# Adafruit_RGB_Matrix_FeatherWing.net
KiCad netlist of a schematic drawn in EAGLE
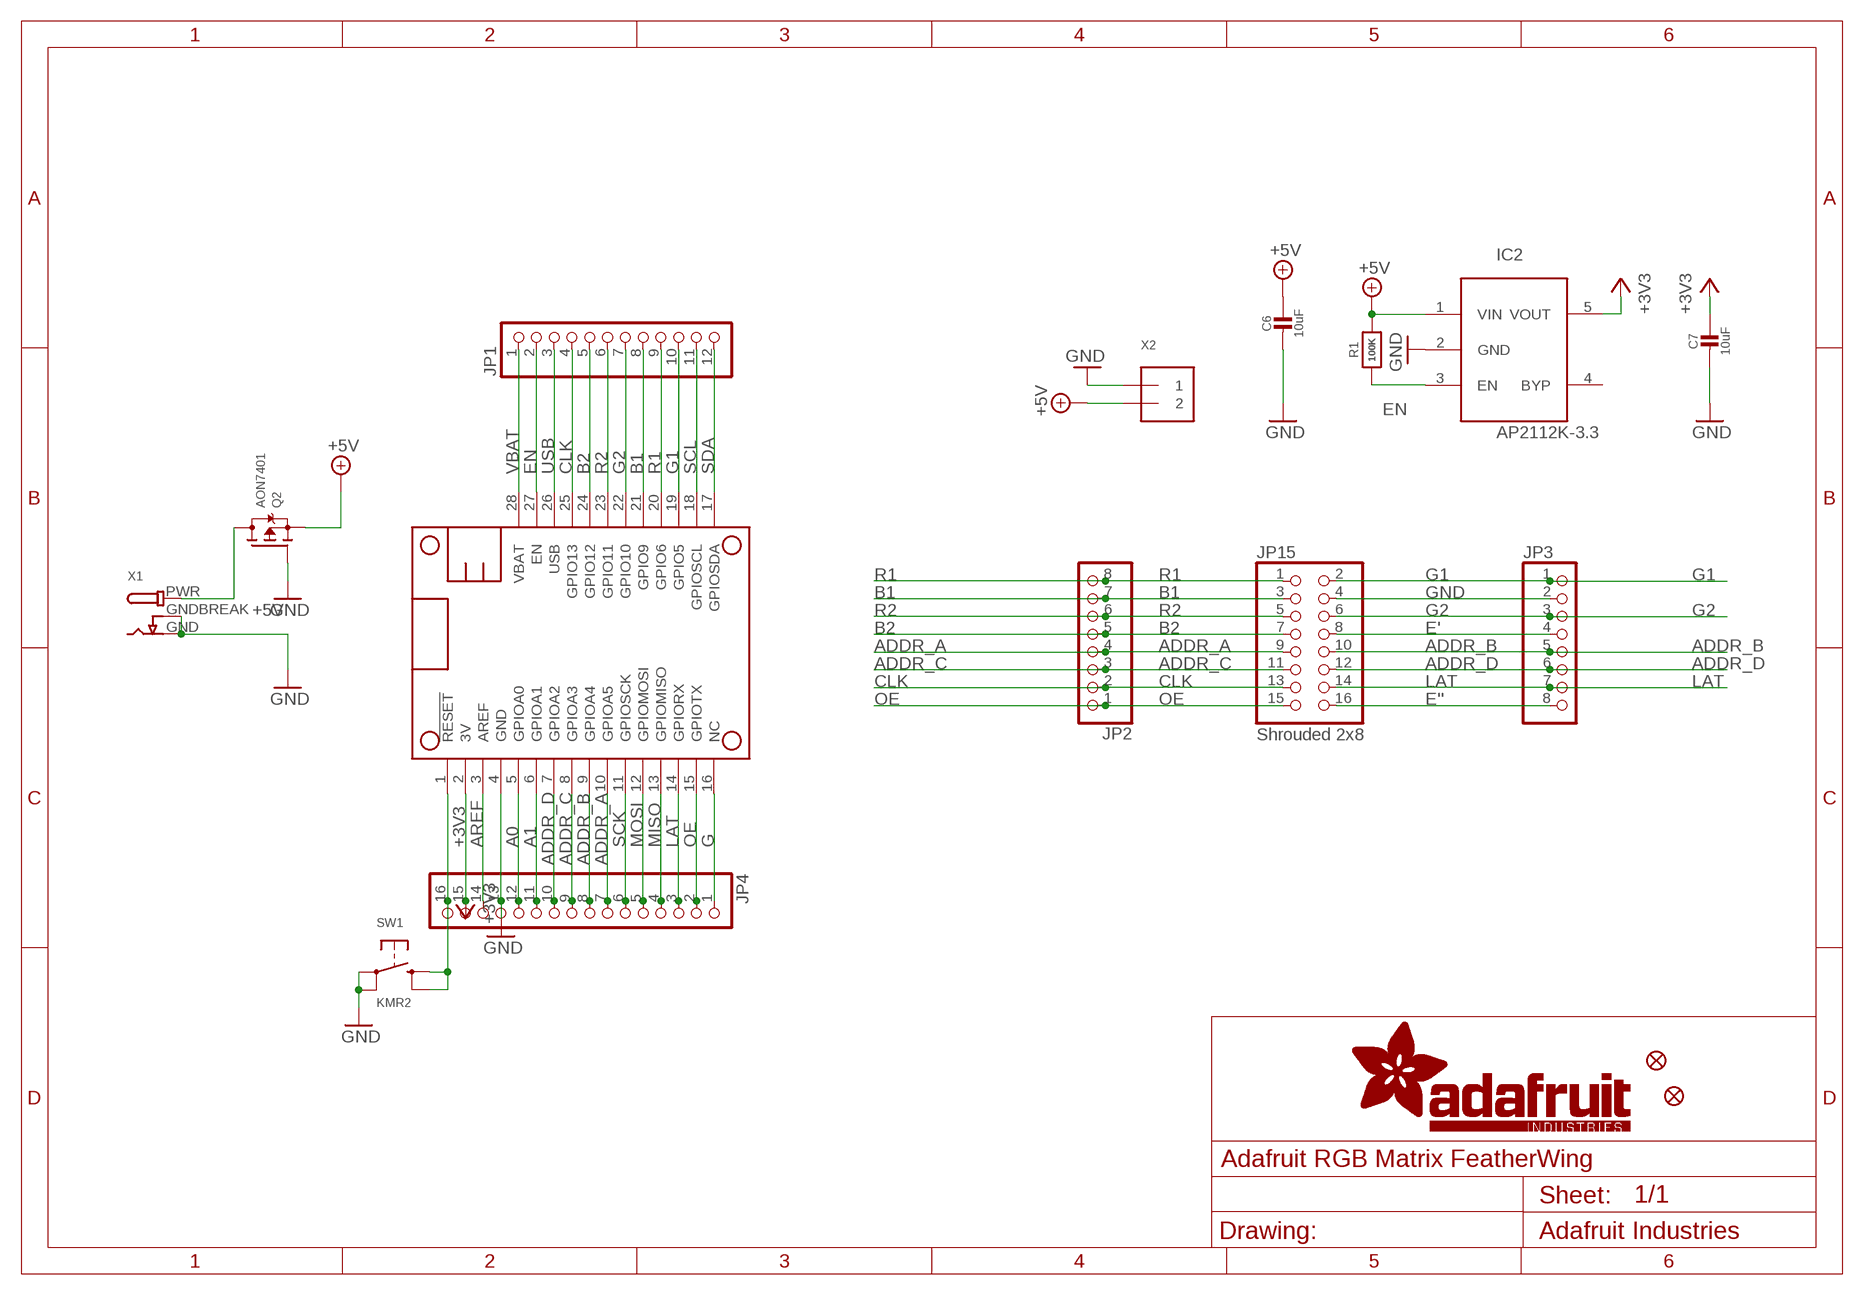
[diagram p0: schematic, sheet 1]

(export (version "E")
  (design (tool "Eeschema 10.0.6"))
  (components
    (comp (ref "C6")
      (value "10uF")
      (footprint "eagle-import:0805-NO")
      (libsource (lib "eagle-import") (part "CAP_CERAMIC0805-NOOUTLINE"))
    )
    (comp (ref "C7")
      (value "10uF")
      (footprint "eagle-import:0805-NO")
      (libsource (lib "eagle-import") (part "CAP_CERAMIC0805-NOOUTLINE"))
    )
    (comp (ref "FID1")
      (value "FIDUCIAL_1MM")
      (footprint "eagle-import:FIDUCIAL_1MM")
      (libsource (lib "eagle-import") (part "FIDUCIAL_1MM"))
    )
    (comp (ref "FID3")
      (value "FIDUCIAL_1MM")
      (footprint "eagle-import:FIDUCIAL_1MM")
      (libsource (lib "eagle-import") (part "FIDUCIAL_1MM"))
    )
    (comp (ref "IC2")
      (value "AP2112K-3.3")
      (footprint "eagle-import:SOT23-5L")
      (libsource (lib "eagle-import") (part "LP298XS"))
    )
    (comp (ref "JP1")
      (value "HEADER-1X12")
      (footprint "eagle-import:1X12_ROUND")
      (libsource (lib "eagle-import") (part "HEADER-1X12"))
    )
    (comp (ref "JP2")
      (value "HEADER-1X870MIL")
      (footprint "eagle-import:1X08_ROUND_70")
      (libsource (lib "eagle-import") (part "HEADER-1X870MIL"))
    )
    (comp (ref "JP3")
      (value "HEADER-1X870MIL")
      (footprint "eagle-import:1X08_ROUND_70")
      (libsource (lib "eagle-import") (part "HEADER-1X870MIL"))
    )
    (comp (ref "JP4")
      (value "HEADER-1X16ROUND")
      (footprint "eagle-import:1X16_ROUND")
      (libsource (lib "eagle-import") (part "HEADER-1X16ROUND"))
    )
    (comp (ref "JP15")
      (value "Shrouded 2x8")
      (footprint "eagle-import:2X08_SHROUDED")
      (libsource (lib "eagle-import") (part "HEADER-2X8_SHROUDED"))
    )
    (comp (ref "MS1")
      (value "FEATHERWING")
      (footprint "eagle-import:FEATHERWING")
      (libsource (lib "eagle-import") (part "FEATHERWING"))
    )
    (comp (ref "Q2")
      (value "AON7401")
      (footprint "eagle-import:POWERDI3333")
      (libsource (lib "eagle-import") (part "MOSFET-P-POWERDI3333"))
    )
    (comp (ref "R1")
      (value "100K")
      (footprint "eagle-import:0603-NO")
      (libsource (lib "eagle-import") (part "RESISTOR_0603_NOOUT"))
    )
    (comp (ref "SW1")
      (value "KMR2")
      (footprint "eagle-import:BTN_KMR2_4.6X2.8")
      (libsource (lib "eagle-import") (part "SWITCH_TACT_SMT4.6X2.8"))
    )
    (comp (ref "X1")
      (value "DCBARRELPTH")
      (footprint "eagle-import:DCJACK_2MM_PTH")
      (libsource (lib "eagle-import") (part "DCBARRELPTH"))
    )
    (comp (ref "X2")
      (value "TERMBLOCK_1X2_5.08MM")
      (footprint "eagle-import:TERMBLOCK_508_1X2")
      (libsource (lib "eagle-import") (part "TERMBLOCK_1X2_5.08MM"))
    )
  )
  (nets
    (net (code "1") (name "+3V3") (class "Default")
      (node (ref "C7") (pin "1") (pinfunction "1_1") (pintype "passive"))
      (node (ref "IC2") (pin "5") (pinfunction "VOUT_5") (pintype "bidirectional"))
      (node (ref "JP4") (pin "15") (pinfunction "15_15") (pintype "passive"))
      (node (ref "MS1") (pin "2") (pinfunction "3V_2") (pintype "power_in"))
    )
    (net (code "2") (name "+5V") (class "Default")
      (node (ref "C6") (pin "1") (pinfunction "1_1") (pintype "passive"))
      (node (ref "IC2") (pin "1") (pinfunction "VIN_1") (pintype "bidirectional"))
      (node (ref "Q2") (pin "1") (pinfunction "S_1") (pintype "passive"))
      (node (ref "Q2") (pin "2") (pinfunction "S_2") (pintype "passive"))
      (node (ref "Q2") (pin "3") (pinfunction "S_3") (pintype "passive"))
      (node (ref "R1") (pin "2") (pinfunction "2_2") (pintype "passive"))
      (node (ref "X2") (pin "P$4") (pinfunction "2_P$4") (pintype "passive"))
    )
    (net (code "3") (name "/A0") (class "Default")
      (node (ref "JP4") (pin "12") (pinfunction "12_12") (pintype "passive"))
      (node (ref "MS1") (pin "5") (pinfunction "GPIOA0_5") (pintype "bidirectional"))
    )
    (net (code "4") (name "/A1") (class "Default")
      (node (ref "JP4") (pin "11") (pinfunction "11_11") (pintype "passive"))
      (node (ref "MS1") (pin "6") (pinfunction "GPIOA1_6") (pintype "bidirectional"))
    )
    (net (code "5") (name "/ADDR_A") (class "Default")
      (node (ref "JP15") (pin "9") (pinfunction "9_9") (pintype "passive"))
      (node (ref "JP2") (pin "4") (pinfunction "4_4") (pintype "passive"))
      (node (ref "JP4") (pin "7") (pinfunction "7_7") (pintype "passive"))
      (node (ref "MS1") (pin "10") (pinfunction "GPIOA5_10") (pintype "bidirectional"))
    )
    (net (code "6") (name "/ADDR_B") (class "Default")
      (node (ref "JP15") (pin "10") (pinfunction "10_10") (pintype "passive"))
      (node (ref "JP3") (pin "5") (pinfunction "5_5") (pintype "passive"))
      (node (ref "JP4") (pin "8") (pinfunction "8_8") (pintype "passive"))
      (node (ref "MS1") (pin "9") (pinfunction "GPIOA4_9") (pintype "bidirectional"))
    )
    (net (code "7") (name "/ADDR_C") (class "Default")
      (node (ref "JP15") (pin "11") (pinfunction "11_11") (pintype "passive"))
      (node (ref "JP2") (pin "3") (pinfunction "3_3") (pintype "passive"))
      (node (ref "JP4") (pin "9") (pinfunction "9_9") (pintype "passive"))
      (node (ref "MS1") (pin "8") (pinfunction "GPIOA3_8") (pintype "bidirectional"))
    )
    (net (code "8") (name "/ADDR_D") (class "Default")
      (node (ref "JP15") (pin "12") (pinfunction "12_12") (pintype "passive"))
      (node (ref "JP3") (pin "6") (pinfunction "6_6") (pintype "passive"))
      (node (ref "JP4") (pin "10") (pinfunction "10_10") (pintype "passive"))
      (node (ref "MS1") (pin "7") (pinfunction "GPIOA2_7") (pintype "bidirectional"))
    )
    (net (code "9") (name "/AREF") (class "Default")
      (node (ref "JP4") (pin "14") (pinfunction "14_14") (pintype "passive"))
      (node (ref "MS1") (pin "3") (pinfunction "AREF_3") (pintype "passive"))
    )
    (net (code "10") (name "/B1") (class "Default")
      (node (ref "JP1") (pin "8") (pinfunction "8_8") (pintype "passive"))
      (node (ref "JP15") (pin "3") (pinfunction "3_3") (pintype "passive"))
      (node (ref "JP2") (pin "7") (pinfunction "7_7") (pintype "passive"))
      (node (ref "MS1") (pin "21") (pinfunction "GPIO9_21") (pintype "bidirectional"))
    )
    (net (code "11") (name "/B2") (class "Default")
      (node (ref "JP1") (pin "5") (pinfunction "5_5") (pintype "passive"))
      (node (ref "JP15") (pin "7") (pinfunction "7_7") (pintype "passive"))
      (node (ref "JP2") (pin "5") (pinfunction "5_5") (pintype "passive"))
      (node (ref "MS1") (pin "24") (pinfunction "GPIO12_24") (pintype "bidirectional"))
    )
    (net (code "12") (name "/CLK") (class "Default")
      (node (ref "JP1") (pin "4") (pinfunction "4_4") (pintype "passive"))
      (node (ref "JP15") (pin "13") (pinfunction "13_13") (pintype "passive"))
      (node (ref "JP2") (pin "2") (pinfunction "2_2") (pintype "passive"))
      (node (ref "MS1") (pin "25") (pinfunction "GPIO13_25") (pintype "bidirectional"))
    )
    (net (code "13") (name "/E'") (class "Default")
      (node (ref "JP15") (pin "8") (pinfunction "8_8") (pintype "passive"))
      (node (ref "JP3") (pin "4") (pinfunction "4_4") (pintype "passive"))
    )
    (net (code "14") (name "/E''") (class "Default")
      (node (ref "JP15") (pin "16") (pinfunction "16_16") (pintype "passive"))
      (node (ref "JP3") (pin "8") (pinfunction "8_8") (pintype "passive"))
    )
    (net (code "15") (name "/EN") (class "Default")
      (node (ref "IC2") (pin "3") (pinfunction "EN_3") (pintype "bidirectional"))
      (node (ref "JP1") (pin "2") (pinfunction "2_2") (pintype "passive"))
      (node (ref "MS1") (pin "27") (pinfunction "EN_27") (pintype "passive"))
      (node (ref "R1") (pin "1") (pinfunction "1_1") (pintype "passive"))
    )
    (net (code "16") (name "/G") (class "Default")
      (node (ref "JP4") (pin "1") (pinfunction "1_1") (pintype "passive"))
      (node (ref "MS1") (pin "16") (pinfunction "NC_16") (pintype "passive"))
    )
    (net (code "17") (name "/G1") (class "Default")
      (node (ref "JP1") (pin "10") (pinfunction "10_10") (pintype "passive"))
      (node (ref "JP15") (pin "2") (pinfunction "2_2") (pintype "passive"))
      (node (ref "JP3") (pin "1") (pinfunction "1_1") (pintype "passive"))
      (node (ref "MS1") (pin "19") (pinfunction "GPIO5_19") (pintype "bidirectional"))
    )
    (net (code "18") (name "/G2") (class "Default")
      (node (ref "JP1") (pin "7") (pinfunction "7_7") (pintype "passive"))
      (node (ref "JP15") (pin "6") (pinfunction "6_6") (pintype "passive"))
      (node (ref "JP3") (pin "3") (pinfunction "3_3") (pintype "passive"))
      (node (ref "MS1") (pin "22") (pinfunction "GPIO10_22") (pintype "bidirectional"))
    )
    (net (code "19") (name "/LAT") (class "Default")
      (node (ref "JP15") (pin "14") (pinfunction "14_14") (pintype "passive"))
      (node (ref "JP3") (pin "7") (pinfunction "7_7") (pintype "passive"))
      (node (ref "JP4") (pin "3") (pinfunction "3_3") (pintype "passive"))
      (node (ref "MS1") (pin "14") (pinfunction "GPIORX_14") (pintype "bidirectional"))
    )
    (net (code "20") (name "/MISO") (class "Default")
      (node (ref "JP4") (pin "4") (pinfunction "4_4") (pintype "passive"))
      (node (ref "MS1") (pin "13") (pinfunction "GPIOMISO_13") (pintype "bidirectional"))
    )
    (net (code "21") (name "/MOSI") (class "Default")
      (node (ref "JP4") (pin "5") (pinfunction "5_5") (pintype "passive"))
      (node (ref "MS1") (pin "12") (pinfunction "GPIOMOSI_12") (pintype "bidirectional"))
    )
    (net (code "22") (name "/OE") (class "Default")
      (node (ref "JP15") (pin "15") (pinfunction "15_15") (pintype "passive"))
      (node (ref "JP2") (pin "1") (pinfunction "1_1") (pintype "passive"))
      (node (ref "JP4") (pin "2") (pinfunction "2_2") (pintype "passive"))
      (node (ref "MS1") (pin "15") (pinfunction "GPIOTX_15") (pintype "bidirectional"))
    )
    (net (code "23") (name "/R1") (class "Default")
      (node (ref "JP1") (pin "9") (pinfunction "9_9") (pintype "passive"))
      (node (ref "JP15") (pin "1") (pinfunction "1_1") (pintype "passive"))
      (node (ref "JP2") (pin "8") (pinfunction "8_8") (pintype "passive"))
      (node (ref "MS1") (pin "20") (pinfunction "GPIO6_20") (pintype "bidirectional"))
    )
    (net (code "24") (name "/R2") (class "Default")
      (node (ref "JP1") (pin "6") (pinfunction "6_6") (pintype "passive"))
      (node (ref "JP15") (pin "5") (pinfunction "5_5") (pintype "passive"))
      (node (ref "JP2") (pin "6") (pinfunction "6_6") (pintype "passive"))
      (node (ref "MS1") (pin "23") (pinfunction "GPIO11_23") (pintype "bidirectional"))
    )
    (net (code "25") (name "/SCK") (class "Default")
      (node (ref "JP4") (pin "6") (pinfunction "6_6") (pintype "passive"))
      (node (ref "MS1") (pin "11") (pinfunction "GPIOSCK_11") (pintype "bidirectional"))
    )
    (net (code "26") (name "/SCL") (class "Default")
      (node (ref "JP1") (pin "11") (pinfunction "11_11") (pintype "passive"))
      (node (ref "MS1") (pin "18") (pinfunction "GPIOSCL_18") (pintype "bidirectional"))
    )
    (net (code "27") (name "/SDA") (class "Default")
      (node (ref "JP1") (pin "12") (pinfunction "12_12") (pintype "passive"))
      (node (ref "MS1") (pin "17") (pinfunction "GPIOSDA_17") (pintype "bidirectional"))
    )
    (net (code "28") (name "/USB") (class "Default")
      (node (ref "JP1") (pin "3") (pinfunction "3_3") (pintype "passive"))
      (node (ref "MS1") (pin "26") (pinfunction "USB_26") (pintype "power_in"))
    )
    (net (code "29") (name "/VBAT") (class "Default")
      (node (ref "JP1") (pin "1") (pinfunction "1_1") (pintype "passive"))
      (node (ref "MS1") (pin "28") (pinfunction "VBAT_28") (pintype "power_in"))
    )
    (net (code "30") (name "GND") (class "Default")
      (node (ref "C6") (pin "2") (pinfunction "2_2") (pintype "passive"))
      (node (ref "C7") (pin "2") (pinfunction "2_2") (pintype "passive"))
      (node (ref "IC2") (pin "2") (pinfunction "GND_2") (pintype "bidirectional"))
      (node (ref "JP15") (pin "4") (pinfunction "4_4") (pintype "passive"))
      (node (ref "JP3") (pin "2") (pinfunction "2_2") (pintype "passive"))
      (node (ref "JP4") (pin "13") (pinfunction "13_13") (pintype "passive"))
      (node (ref "MS1") (pin "4") (pinfunction "GND_4") (pintype "power_in"))
      (node (ref "Q2") (pin "4") (pinfunction "G_4") (pintype "passive"))
      (node (ref "SW1") (pin "A") (pinfunction "P_A") (pintype "passive"))
      (node (ref "SW1") (pin "A'") (pinfunction "P1_A'") (pintype "passive"))
      (node (ref "X1") (pin "GND") (pinfunction "GND_GND") (pintype "power_in"))
      (node (ref "X1") (pin "GNDBREAK") (pinfunction "GNDBREAK_GNDBREAK") (pintype "power_in"))
      (node (ref "X2") (pin "P$3") (pinfunction "1_P$3") (pintype "passive"))
    )
    (net (code "31") (name "Net-(MS1-~{RESET})") (class "Default")
      (node (ref "JP4") (pin "16") (pinfunction "16_16") (pintype "passive"))
      (node (ref "MS1") (pin "1") (pinfunction "~{RESET}_1") (pintype "input"))
      (node (ref "SW1") (pin "B") (pinfunction "S_B") (pintype "passive"))
      (node (ref "SW1") (pin "B'") (pinfunction "S1_B'") (pintype "passive"))
    )
    (net (code "32") (name "Net-(Q2-D)") (class "Default")
      (node (ref "Q2") (pin "5678") (pinfunction "D_5678") (pintype "passive"))
      (node (ref "X1") (pin "PWR") (pinfunction "PWR_PWR") (pintype "power_in"))
    )
    (net (code "33") (name "unconnected-(IC2-BYP-Pad4)") (class "Default")
      (node (ref "IC2") (pin "4") (pinfunction "BYP_4") (pintype "bidirectional"))
    )
  )
)
